# 7V4_1.net
KiCad netlist of a schematic drawn in Altium Designer
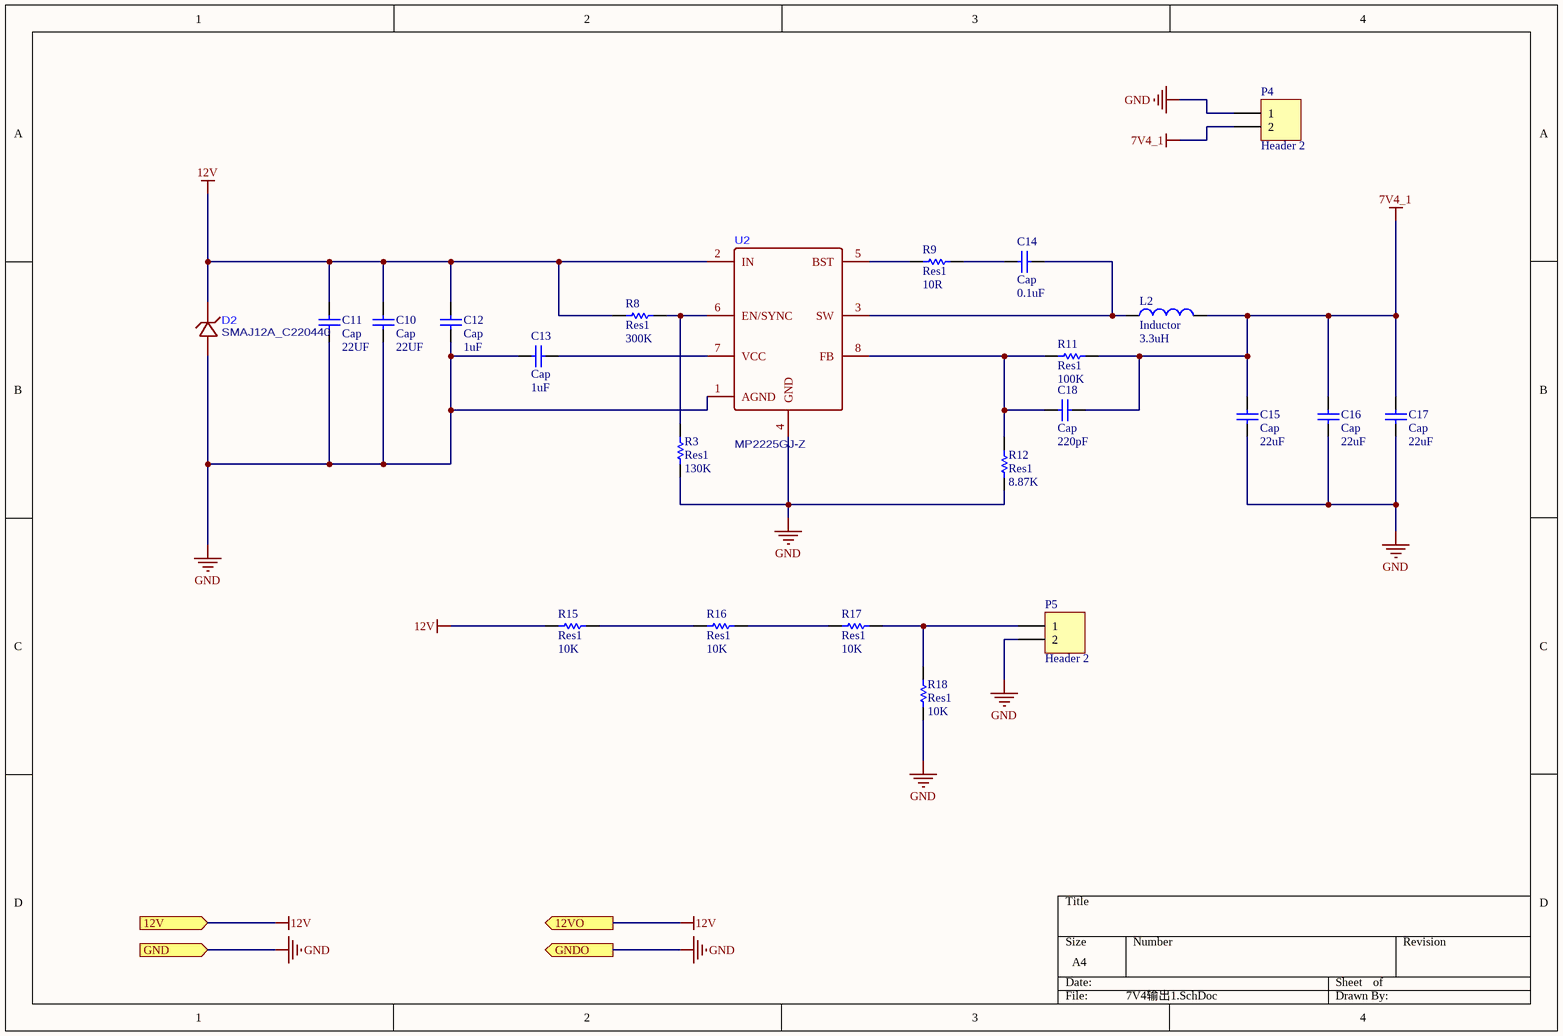
[diagram p0: 7V4输出1.SchDoc]

(export (version "E")
  (design (tool "Eeschema 10.0.6"))
  (components
    (comp (ref "C10")
      (value "Cap")
      (footprint "C1206")
      (description "Capacitor")
      (fields (field (name "ALTIUM_VALUE") "22UF") (field (name "PUBLISHER") "Altium Limited"))
      (libsource (lib "Miscellaneous Devices") (part "Cap"))
    )
    (comp (ref "C11")
      (value "Cap")
      (footprint "C1206")
      (description "Capacitor")
      (fields (field (name "ALTIUM_VALUE") "22UF") (field (name "PUBLISHER") "Altium Limited"))
      (libsource (lib "Miscellaneous Devices") (part "Cap"))
    )
    (comp (ref "C12")
      (value "Cap")
      (footprint "R0603")
      (description "Capacitor")
      (fields (field (name "ALTIUM_VALUE") "1uF") (field (name "PUBLISHER") "Altium Limited"))
      (libsource (lib "Miscellaneous Devices") (part "Cap"))
    )
    (comp (ref "C13")
      (value "Cap")
      (footprint "R0603")
      (description "Capacitor")
      (fields (field (name "ALTIUM_VALUE") "1uF") (field (name "PUBLISHER") "Altium Limited"))
      (libsource (lib "Miscellaneous Devices") (part "Cap"))
    )
    (comp (ref "C14")
      (value "Cap")
      (footprint "R0603")
      (description "Capacitor")
      (fields (field (name "ALTIUM_VALUE") "0.1uF") (field (name "PUBLISHER") "Altium Limited"))
      (libsource (lib "Miscellaneous Devices") (part "Cap"))
    )
    (comp (ref "C15")
      (value "Cap")
      (footprint "C0805")
      (description "Capacitor")
      (fields (field (name "ALTIUM_VALUE") "22uF") (field (name "PUBLISHER") "Altium Limited"))
      (libsource (lib "Miscellaneous Devices") (part "Cap"))
    )
    (comp (ref "C16")
      (value "Cap")
      (footprint "C0805")
      (description "Capacitor")
      (fields (field (name "ALTIUM_VALUE") "22uF") (field (name "PUBLISHER") "Altium Limited"))
      (libsource (lib "Miscellaneous Devices") (part "Cap"))
    )
    (comp (ref "C17")
      (value "Cap")
      (footprint "C0805")
      (description "Capacitor")
      (fields (field (name "ALTIUM_VALUE") "22uF") (field (name "PUBLISHER") "Altium Limited"))
      (libsource (lib "Miscellaneous Devices") (part "Cap"))
    )
    (comp (ref "C18")
      (value "Cap")
      (footprint "R0603")
      (description "Capacitor")
      (fields (field (name "ALTIUM_VALUE") "220pF") (field (name "PUBLISHER") "Altium Limited"))
      (libsource (lib "Miscellaneous Devices") (part "Cap"))
    )
    (comp (ref "D2")
      (value "SMAJ12A_C220440")
      (footprint "SMA_L4.4-W2.8-LS5.4-RD")
      (libsource (lib "SMAJ12A_C220440_2021-10-18") (part "SMAJ12A_C220440"))
    )
    (comp (ref "L2")
      (value "Inductor")
      (footprint "IND-SMD_L7.8-W7.0_MAPM0630F")
      (fields (field (name "ALTIUM_VALUE") "3.3uH") (field (name "PUBLISHER") "Altium Limited"))
      (libsource (lib "Miscellaneous Devices") (part "Inductor"))
    )
    (comp (ref "P4")
      (value "Header 2")
      (footprint "XH2.54-2A")
      (description "Header, 2-Pin")
      (fields (field (name "PUBLISHER") "Altium Limited"))
      (libsource (lib "Miscellaneous Connectors") (part "Header 2"))
    )
    (comp (ref "P5")
      (value "Header 2")
      (footprint "XH2.54-2A")
      (description "Header, 2-Pin")
      (fields (field (name "PUBLISHER") "Altium Limited"))
      (libsource (lib "Miscellaneous Connectors") (part "Header 2"))
    )
    (comp (ref "R3")
      (value "Res1")
      (footprint "R0603")
      (description "Resistor")
      (fields (field (name "ALTIUM_VALUE") "130K") (field (name "PUBLISHER") "Altium Limited"))
      (libsource (lib "Miscellaneous Devices") (part "Res1"))
    )
    (comp (ref "R8")
      (value "Res1")
      (footprint "R0603")
      (description "Resistor")
      (fields (field (name "ALTIUM_VALUE") "300K") (field (name "PUBLISHER") "Altium Limited"))
      (libsource (lib "Miscellaneous Devices") (part "Res1"))
    )
    (comp (ref "R9")
      (value "Res1")
      (footprint "R0603")
      (description "Resistor")
      (fields (field (name "ALTIUM_VALUE") "10R") (field (name "PUBLISHER") "Altium Limited"))
      (libsource (lib "Miscellaneous Devices") (part "Res1"))
    )
    (comp (ref "R11")
      (value "Res1")
      (footprint "R0603")
      (description "Resistor")
      (fields (field (name "ALTIUM_VALUE") "100K") (field (name "PUBLISHER") "Altium Limited"))
      (libsource (lib "Miscellaneous Devices") (part "Res1"))
    )
    (comp (ref "R12")
      (value "Res1")
      (footprint "R0603")
      (description "Resistor")
      (fields (field (name "ALTIUM_VALUE") "8.87K") (field (name "PUBLISHER") "Altium Limited"))
      (libsource (lib "Miscellaneous Devices") (part "Res1"))
    )
    (comp (ref "R15")
      (value "Res1")
      (footprint "R0603")
      (description "Resistor")
      (fields (field (name "ALTIUM_VALUE") "10K") (field (name "PUBLISHER") "Altium Limited"))
      (libsource (lib "Miscellaneous Devices") (part "Res1"))
    )
    (comp (ref "R16")
      (value "Res1")
      (footprint "R0603")
      (description "Resistor")
      (fields (field (name "ALTIUM_VALUE") "10K") (field (name "PUBLISHER") "Altium Limited"))
      (libsource (lib "Miscellaneous Devices") (part "Res1"))
    )
    (comp (ref "R17")
      (value "Res1")
      (footprint "R0603")
      (description "Resistor")
      (fields (field (name "ALTIUM_VALUE") "10K") (field (name "PUBLISHER") "Altium Limited"))
      (libsource (lib "Miscellaneous Devices") (part "Res1"))
    )
    (comp (ref "R18")
      (value "Res1")
      (footprint "R0603")
      (description "Resistor")
      (fields (field (name "ALTIUM_VALUE") "10K") (field (name "PUBLISHER") "Altium Limited"))
      (libsource (lib "Miscellaneous Devices") (part "Res1"))
    )
    (comp (ref "U2")
      (value "MP2225GJ-Z")
      (footprint "TSOT-23-8_L2.9-W1.6-P0.65-LS2.8-BR")
      (libsource (lib "MP2225GJ-Z_2021-10-18") (part "MP2225GJ-Z"))
    )
  )
  (nets
    (net (code "1") (name "7V4_1") (class "Default")
      (node (ref "C15") (pin "2") (pinfunction "2_2") (pintype "passive"))
      (node (ref "C16") (pin "2") (pinfunction "2_2") (pintype "passive"))
      (node (ref "C17") (pin "2") (pinfunction "2_2") (pintype "passive"))
      (node (ref "C18") (pin "2") (pinfunction "2_2") (pintype "passive"))
      (node (ref "L2") (pin "2") (pinfunction "2_2") (pintype "passive"))
      (node (ref "P4") (pin "2") (pinfunction "2_2") (pintype "passive"))
      (node (ref "R11") (pin "2") (pinfunction "2_2") (pintype "passive"))
    )
    (net (code "2") (name "12V") (class "Default")
      (node (ref "C10") (pin "2") (pinfunction "2_2") (pintype "passive"))
      (node (ref "C11") (pin "2") (pinfunction "2_2") (pintype "passive"))
      (node (ref "C12") (pin "2") (pinfunction "2_2") (pintype "passive"))
      (node (ref "D2") (pin "1") (pinfunction "1_1") (pintype "passive"))
      (node (ref "R15") (pin "2") (pinfunction "2_2") (pintype "passive"))
      (node (ref "R8") (pin "1") (pinfunction "1_1") (pintype "passive"))
      (node (ref "U2") (pin "2") (pinfunction "IN_2") (pintype "passive"))
    )
    (net (code "3") (name "GND") (class "Default")
      (node (ref "C10") (pin "1") (pinfunction "1_1") (pintype "passive"))
      (node (ref "C11") (pin "1") (pinfunction "1_1") (pintype "passive"))
      (node (ref "C12") (pin "1") (pinfunction "1_1") (pintype "passive"))
      (node (ref "C13") (pin "1") (pinfunction "1_1") (pintype "passive"))
      (node (ref "C15") (pin "1") (pinfunction "1_1") (pintype "passive"))
      (node (ref "C16") (pin "1") (pinfunction "1_1") (pintype "passive"))
      (node (ref "C17") (pin "1") (pinfunction "1_1") (pintype "passive"))
      (node (ref "D2") (pin "2") (pinfunction "2_2") (pintype "passive"))
      (node (ref "P4") (pin "1") (pinfunction "1_1") (pintype "passive"))
      (node (ref "P5") (pin "2") (pinfunction "2_2") (pintype "passive"))
      (node (ref "R12") (pin "1") (pinfunction "1_1") (pintype "passive"))
      (node (ref "R18") (pin "1") (pinfunction "1_1") (pintype "passive"))
      (node (ref "R3") (pin "1") (pinfunction "1_1") (pintype "passive"))
      (node (ref "U2") (pin "1") (pinfunction "AGND_1") (pintype "passive"))
      (node (ref "U2") (pin "4") (pinfunction "GND_4") (pintype "passive"))
    )
    (net (code "4") (name "Net-(C14-Pad1)") (class "Default")
      (node (ref "C14") (pin "1") (pinfunction "1_1") (pintype "passive"))
      (node (ref "R9") (pin "2") (pinfunction "2_2") (pintype "passive"))
    )
    (net (code "5") (name "Net-(P5-Pad1)") (class "Default")
      (node (ref "P5") (pin "1") (pinfunction "1_1") (pintype "passive"))
      (node (ref "R17") (pin "1") (pinfunction "1_1") (pintype "passive"))
      (node (ref "R18") (pin "2") (pinfunction "2_2") (pintype "passive"))
    )
    (net (code "6") (name "Net-(R15-Pad1)") (class "Default")
      (node (ref "R15") (pin "1") (pinfunction "1_1") (pintype "passive"))
      (node (ref "R16") (pin "2") (pinfunction "2_2") (pintype "passive"))
    )
    (net (code "7") (name "Net-(R16-Pad1)") (class "Default")
      (node (ref "R16") (pin "1") (pinfunction "1_1") (pintype "passive"))
      (node (ref "R17") (pin "2") (pinfunction "2_2") (pintype "passive"))
    )
    (net (code "8") (name "Net-(U2-BST)") (class "Default")
      (node (ref "R9") (pin "1") (pinfunction "1_1") (pintype "passive"))
      (node (ref "U2") (pin "5") (pinfunction "BST_5") (pintype "passive"))
    )
    (net (code "9") (name "Net-(U2-EN{slash}SYNC)") (class "Default")
      (node (ref "R3") (pin "2") (pinfunction "2_2") (pintype "passive"))
      (node (ref "R8") (pin "2") (pinfunction "2_2") (pintype "passive"))
      (node (ref "U2") (pin "6") (pinfunction "EN/SYNC_6") (pintype "passive"))
    )
    (net (code "10") (name "Net-(U2-FB)") (class "Default")
      (node (ref "C18") (pin "1") (pinfunction "1_1") (pintype "passive"))
      (node (ref "R11") (pin "1") (pinfunction "1_1") (pintype "passive"))
      (node (ref "R12") (pin "2") (pinfunction "2_2") (pintype "passive"))
      (node (ref "U2") (pin "8") (pinfunction "FB_8") (pintype "passive"))
    )
    (net (code "11") (name "Net-(U2-SW)") (class "Default")
      (node (ref "C14") (pin "2") (pinfunction "2_2") (pintype "passive"))
      (node (ref "L2") (pin "1") (pinfunction "1_1") (pintype "passive"))
      (node (ref "U2") (pin "3") (pinfunction "SW_3") (pintype "passive"))
    )
    (net (code "12") (name "Net-(U2-VCC)") (class "Default")
      (node (ref "C13") (pin "2") (pinfunction "2_2") (pintype "passive"))
      (node (ref "U2") (pin "7") (pinfunction "VCC_7") (pintype "passive"))
    )
  )
)
